# Sheet1.net
KiCad netlist of a schematic drawn in Altium Designer
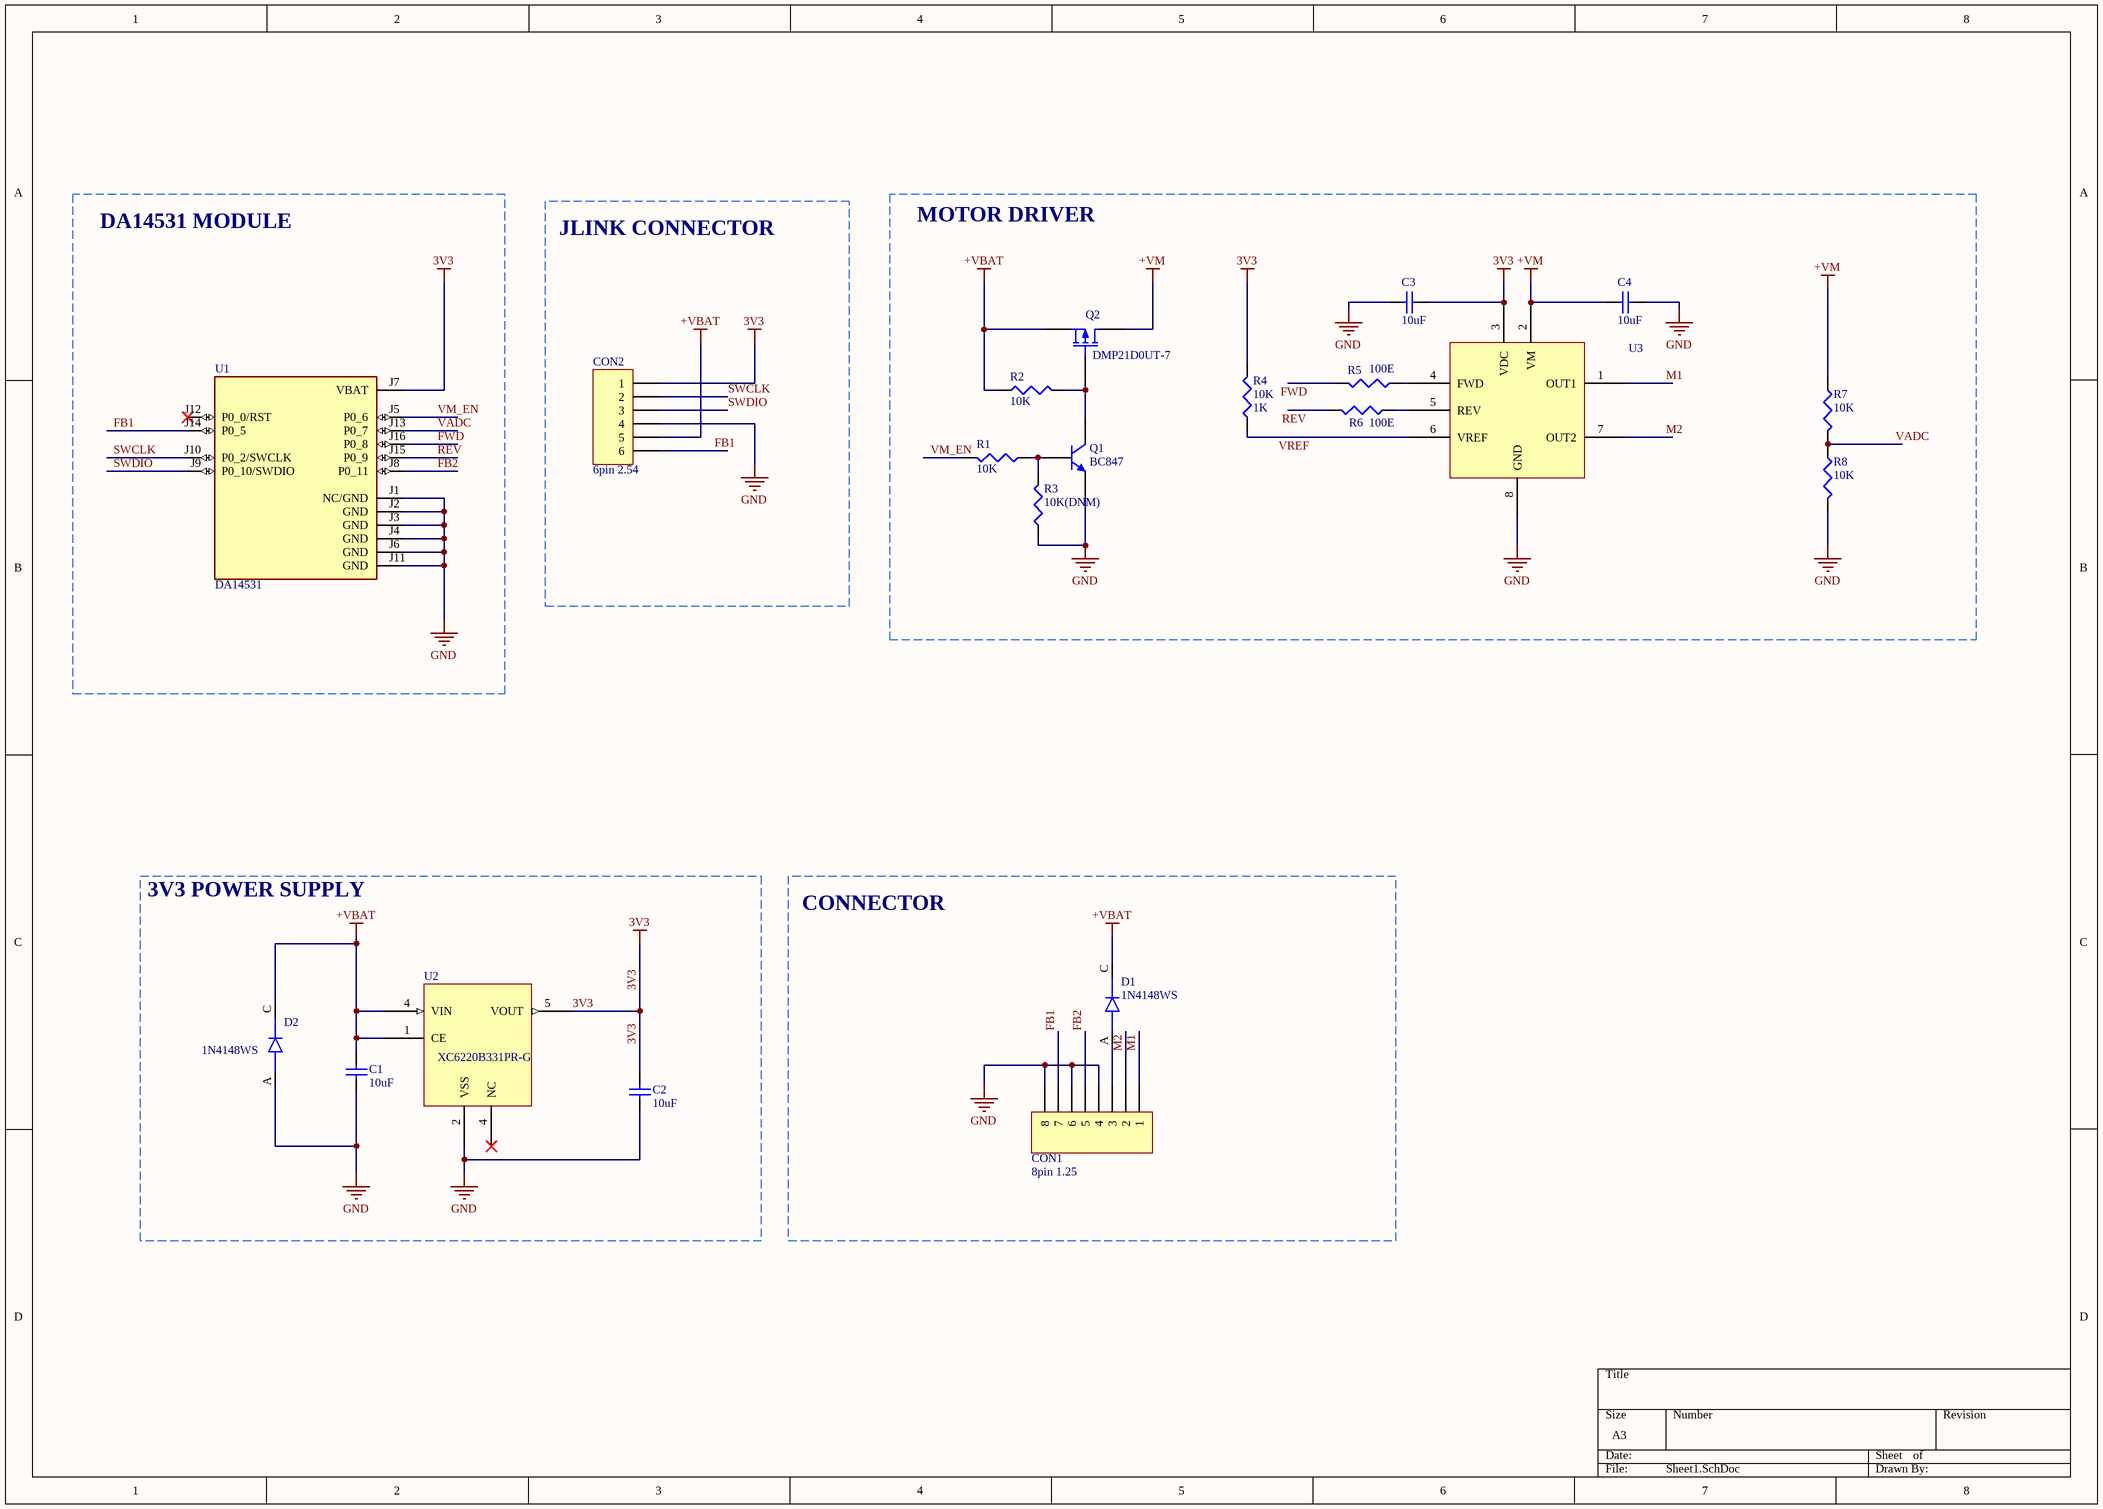
[diagram p0: Sheet1.SchDoc]

(export (version "E")
  (design (tool "Eeschema 10.0.6"))
  (components
    (comp (ref "C1")
      (value "10uF")
      (footprint "0603_C")
      (description "Capacitor")
      (fields (field (name "MFR") "KEMET"))
      (libsource (lib "Miscellaneous Devices") (part "Cap"))
    )
    (comp (ref "C2")
      (value "10uF")
      (footprint "0603_C")
      (description "Capacitor")
      (fields (field (name "MFR") "KEMET"))
      (libsource (lib "Miscellaneous Devices") (part "Cap"))
    )
    (comp (ref "C3")
      (value "10uF")
      (footprint "0603_C")
      (description "Capacitor")
      (fields (field (name "MFR") "KEMET"))
      (libsource (lib "Miscellaneous Devices") (part "Cap"))
    )
    (comp (ref "C4")
      (value "10uF")
      (footprint "0603_C")
      (description "Capacitor")
      (fields (field (name "MFR") "KEMET"))
      (libsource (lib "Miscellaneous Devices") (part "Cap"))
    )
    (comp (ref "CON1")
      (value "8pin 1.25")
      (footprint "8Pin 1.25")
      (libsource (lib "XC6220B331PR-G_SCH") (part "8pin 1.25"))
    )
    (comp (ref "CON2")
      (value "6pin 2.54")
      (footprint "6PIN 2.54")
      (libsource (lib "XC6220B331PR-G_SCH") (part "6pin 2.54"))
    )
    (comp (ref "D1")
      (value "1N4148WS")
      (footprint "SOD323")
      (description "Diode Standard 100V 150mA Surface Mount SOD-123")
      (fields (field (name "MF") "Micro Commercial") (field (name "MP") "1N4148W-TP"))
      (libsource (lib "XC6220B331PR-G_SCH") (part "1N4148W-TP"))
    )
    (comp (ref "D2")
      (value "1N4148WS")
      (footprint "SOD323")
      (description "Diode Standard 100V 150mA Surface Mount SOD-123")
      (fields (field (name "MF") "Micro Commercial") (field (name "MP") "1N4148W-TP"))
      (libsource (lib "XC6220B331PR-G_SCH") (part "1N4148W-TP"))
    )
    (comp (ref "Q1")
      (value "BC847")
      (footprint "BC846")
      (fields (field (name "MFR") "Nexperia"))
      (libsource (lib "XC6220B331PR-G_SCH") (part "BC846X"))
    )
    (comp (ref "Q2")
      (value "Q2")
      (footprint "SOT_523_P_MOS")
      (fields (field (name "PN") "DMP21D0UT-7") (field (name "MFR") "Diodes Incorporated"))
      (libsource (lib "XC6220B331PR-G_SCH") (part "PMOS"))
    )
    (comp (ref "R1")
      (value "10K")
      (footprint "0603_R")
      (description "Resistor")
      (libsource (lib "XC6220B331PR-G_SCH") (part "Res3"))
    )
    (comp (ref "R2")
      (value "10K")
      (footprint "0603_R")
      (description "Resistor")
      (libsource (lib "XC6220B331PR-G_SCH") (part "Res3"))
    )
    (comp (ref "R3")
      (value "10K(DNM)")
      (footprint "0603_R")
      (description "Resistor")
      (libsource (lib "XC6220B331PR-G_SCH") (part "Res3"))
    )
    (comp (ref "R4")
      (value "10K")
      (footprint "0603_R")
      (description "Resistor")
      (fields (field (name "ALTIUM_VALUE") "1K") (field (name "PUBLISHER") "Altium Limited"))
      (libsource (lib "XC6220B331PR-G_SCH") (part "Res3"))
    )
    (comp (ref "R5")
      (value "100E")
      (footprint "0603_R")
      (description "Resistor")
      (libsource (lib "XC6220B331PR-G_SCH") (part "Res3"))
    )
    (comp (ref "R6")
      (value "100E")
      (footprint "0603_R")
      (description "Resistor")
      (libsource (lib "XC6220B331PR-G_SCH") (part "Res3"))
    )
    (comp (ref "R7")
      (value "10K")
      (footprint "0603_R")
      (description "Resistor")
      (libsource (lib "XC6220B331PR-G_SCH") (part "Res3"))
    )
    (comp (ref "R8")
      (value "10K")
      (footprint "0603_R")
      (description "Resistor")
      (libsource (lib "XC6220B331PR-G_SCH") (part "Res3"))
    )
    (comp (ref "U1")
      (value "DA14531")
      (footprint "DA14531")
      (fields (field (name "MFR") "Dialog Semiconductor"))
      (libsource (lib "XC6220B331PR-G_SCH") (part "DA14531"))
    )
    (comp (ref "U2")
      (value "XC6220B331PR-G")
      (footprint "CONV_AL8861Y-13")
      (fields (field (name "MFR") "Torex Semiconductor Ltd"))
      (libsource (lib "XC6220B331PR-G_SCH") (part "Component_1"))
    )
    (comp (ref "U3")
      (value "ZXBM5210")
      (footprint "SOIC127P600X180-8N")
      (libsource (lib "XC6220B331PR-G_SCH") (part "ZXBM5210"))
    )
  )
  (nets
    (net (code "1") (name "+VBAT") (class "Default")
      (node (ref "C1") (pin "2") (pinfunction "2_2") (pintype "passive"))
      (node (ref "CON2") (pin "5") (pinfunction "5_5") (pintype "passive"))
      (node (ref "D1") (pin "C") (pinfunction "C_C") (pintype "passive"))
      (node (ref "D2") (pin "C") (pinfunction "C_C") (pintype "passive"))
      (node (ref "Q2") (pin "3") (pinfunction "S_3") (pintype "passive"))
      (node (ref "R2") (pin "1") (pinfunction "1_1") (pintype "passive"))
      (node (ref "U2") (pin "1") (pinfunction "CE_1") (pintype "passive"))
      (node (ref "U2") (pin "4") (pinfunction "VIN_4") (pintype "input"))
    )
    (net (code "2") (name "+VM") (class "Default")
      (node (ref "C4") (pin "2") (pinfunction "2_2") (pintype "passive"))
      (node (ref "Q2") (pin "1") (pinfunction "D_1") (pintype "passive"))
      (node (ref "R7") (pin "1") (pinfunction "1_1") (pintype "passive"))
      (node (ref "U3") (pin "2") (pinfunction "VM_2") (pintype "passive"))
    )
    (net (code "3") (name "/FB1") (class "Default")
      (node (ref "CON1") (pin "7") (pinfunction "7_7") (pintype "passive"))
      (node (ref "CON2") (pin "6") (pinfunction "6_6") (pintype "passive"))
      (node (ref "U1") (pin "J14") (pinfunction "P0_5_J14") (pintype "bidirectional"))
    )
    (net (code "4") (name "/FB2") (class "Default")
      (node (ref "CON1") (pin "5") (pinfunction "5_5") (pintype "passive"))
      (node (ref "U1") (pin "J8") (pinfunction "P0_11_J8") (pintype "bidirectional"))
    )
    (net (code "5") (name "/FWD") (class "Default")
      (node (ref "R5") (pin "2") (pinfunction "2_2") (pintype "passive"))
      (node (ref "U1") (pin "J16") (pinfunction "P0_8_J16") (pintype "bidirectional"))
    )
    (net (code "6") (name "/M1") (class "Default")
      (node (ref "CON1") (pin "1") (pinfunction "1_1") (pintype "passive"))
      (node (ref "U3") (pin "1") (pinfunction "OUT1_1") (pintype "passive"))
    )
    (net (code "7") (name "/M2") (class "Default")
      (node (ref "CON1") (pin "2") (pinfunction "2_2") (pintype "passive"))
      (node (ref "U3") (pin "7") (pinfunction "OUT2_7") (pintype "passive"))
    )
    (net (code "8") (name "/REV") (class "Default")
      (node (ref "R6") (pin "2") (pinfunction "2_2") (pintype "passive"))
      (node (ref "U1") (pin "J15") (pinfunction "P0_9_J15") (pintype "bidirectional"))
    )
    (net (code "9") (name "/SWCLK") (class "Default")
      (node (ref "CON2") (pin "2") (pinfunction "2_2") (pintype "passive"))
      (node (ref "U1") (pin "J10") (pinfunction "P0_2/SWCLK_J10") (pintype "bidirectional"))
    )
    (net (code "10") (name "/SWDIO") (class "Default")
      (node (ref "CON2") (pin "3") (pinfunction "3_3") (pintype "passive"))
      (node (ref "U1") (pin "J9") (pinfunction "P0_10/SWDIO_J9") (pintype "bidirectional"))
    )
    (net (code "11") (name "/VADC") (class "Default")
      (node (ref "R7") (pin "2") (pinfunction "2_2") (pintype "passive"))
      (node (ref "R8") (pin "1") (pinfunction "1_1") (pintype "passive"))
      (node (ref "U1") (pin "J13") (pinfunction "P0_7_J13") (pintype "bidirectional"))
    )
    (net (code "12") (name "/VM_EN") (class "Default")
      (node (ref "R1") (pin "2") (pinfunction "2_2") (pintype "passive"))
      (node (ref "U1") (pin "J5") (pinfunction "P0_6_J5") (pintype "bidirectional"))
    )
    (net (code "13") (name "/VREF") (class "Default")
      (node (ref "R4") (pin "1") (pinfunction "1_1") (pintype "passive"))
      (node (ref "U3") (pin "6") (pinfunction "VREF_6") (pintype "passive"))
    )
    (net (code "14") (name "3V3") (class "Default")
      (node (ref "C2") (pin "2") (pinfunction "2_2") (pintype "passive"))
      (node (ref "C3") (pin "2") (pinfunction "2_2") (pintype "passive"))
      (node (ref "CON2") (pin "1") (pinfunction "1_1") (pintype "passive"))
      (node (ref "R4") (pin "2") (pinfunction "2_2") (pintype "passive"))
      (node (ref "U1") (pin "J7") (pinfunction "VBAT_J7") (pintype "power_in"))
      (node (ref "U2") (pin "5") (pinfunction "VOUT_5") (pintype "output"))
      (node (ref "U3") (pin "3") (pinfunction "VDC_3") (pintype "passive"))
    )
    (net (code "15") (name "GND") (class "Default")
      (node (ref "C1") (pin "1") (pinfunction "1_1") (pintype "passive"))
      (node (ref "C2") (pin "1") (pinfunction "1_1") (pintype "passive"))
      (node (ref "C3") (pin "1") (pinfunction "1_1") (pintype "passive"))
      (node (ref "C4") (pin "1") (pinfunction "1_1") (pintype "passive"))
      (node (ref "CON1") (pin "4") (pinfunction "4_4") (pintype "passive"))
      (node (ref "CON1") (pin "6") (pinfunction "6_6") (pintype "passive"))
      (node (ref "CON1") (pin "8") (pinfunction "8_8") (pintype "passive"))
      (node (ref "CON2") (pin "4") (pinfunction "4_4") (pintype "passive"))
      (node (ref "D2") (pin "A") (pinfunction "A_A") (pintype "passive"))
      (node (ref "Q1") (pin "2") (pinfunction "E_2") (pintype "passive"))
      (node (ref "R3") (pin "1") (pinfunction "1_1") (pintype "passive"))
      (node (ref "R8") (pin "2") (pinfunction "2_2") (pintype "passive"))
      (node (ref "U1") (pin "J1") (pinfunction "NC/GND_J1") (pintype "passive"))
      (node (ref "U1") (pin "J11") (pinfunction "GND_J11") (pintype "power_in"))
      (node (ref "U1") (pin "J2") (pinfunction "GND_J2") (pintype "power_in"))
      (node (ref "U1") (pin "J3") (pinfunction "GND_J3") (pintype "power_in"))
      (node (ref "U1") (pin "J4") (pinfunction "GND_J4") (pintype "power_in"))
      (node (ref "U1") (pin "J6") (pinfunction "GND_J6") (pintype "power_in"))
      (node (ref "U2") (pin "2") (pinfunction "VSS_2") (pintype "passive"))
      (node (ref "U3") (pin "8") (pinfunction "GND_8") (pintype "passive"))
    )
    (net (code "16") (name "Net-(CON1-Pad3)") (class "Default")
      (node (ref "CON1") (pin "3") (pinfunction "3_3") (pintype "passive"))
      (node (ref "D1") (pin "A") (pinfunction "A_A") (pintype "passive"))
    )
    (net (code "17") (name "Net-(Q1-B)") (class "Default")
      (node (ref "Q1") (pin "3") (pinfunction "B_3") (pintype "passive"))
      (node (ref "R1") (pin "1") (pinfunction "1_1") (pintype "passive"))
      (node (ref "R3") (pin "2") (pinfunction "2_2") (pintype "passive"))
    )
    (net (code "18") (name "Net-(Q1-C)") (class "Default")
      (node (ref "Q1") (pin "1") (pinfunction "C_1") (pintype "passive"))
      (node (ref "Q2") (pin "2") (pinfunction "G_2") (pintype "passive"))
      (node (ref "R2") (pin "2") (pinfunction "2_2") (pintype "passive"))
    )
    (net (code "19") (name "Net-(U3-FWD)") (class "Default")
      (node (ref "R5") (pin "1") (pinfunction "1_1") (pintype "passive"))
      (node (ref "U3") (pin "4") (pinfunction "FWD_4") (pintype "passive"))
    )
    (net (code "20") (name "Net-(U3-REV)") (class "Default")
      (node (ref "R6") (pin "1") (pinfunction "1_1") (pintype "passive"))
      (node (ref "U3") (pin "5") (pinfunction "REV_5") (pintype "passive"))
    )
    (net (code "21") (name "unconnected-(U1-P0_0{slash}RST-PadJ12)") (class "Default")
      (node (ref "U1") (pin "J12") (pinfunction "P0_0/RST_J12") (pintype "bidirectional+no_connect"))
    )
    (net (code "22") (name "unconnected-(U2-NC-Pad4)") (class "Default")
      (node (ref "U2") (pin "4") (pinfunction "NC_4") (pintype "passive+no_connect"))
    )
  )
)
